# 2_Airframe-Power_2_-_Old.net
KiCad netlist of a schematic drawn in Altium Designer
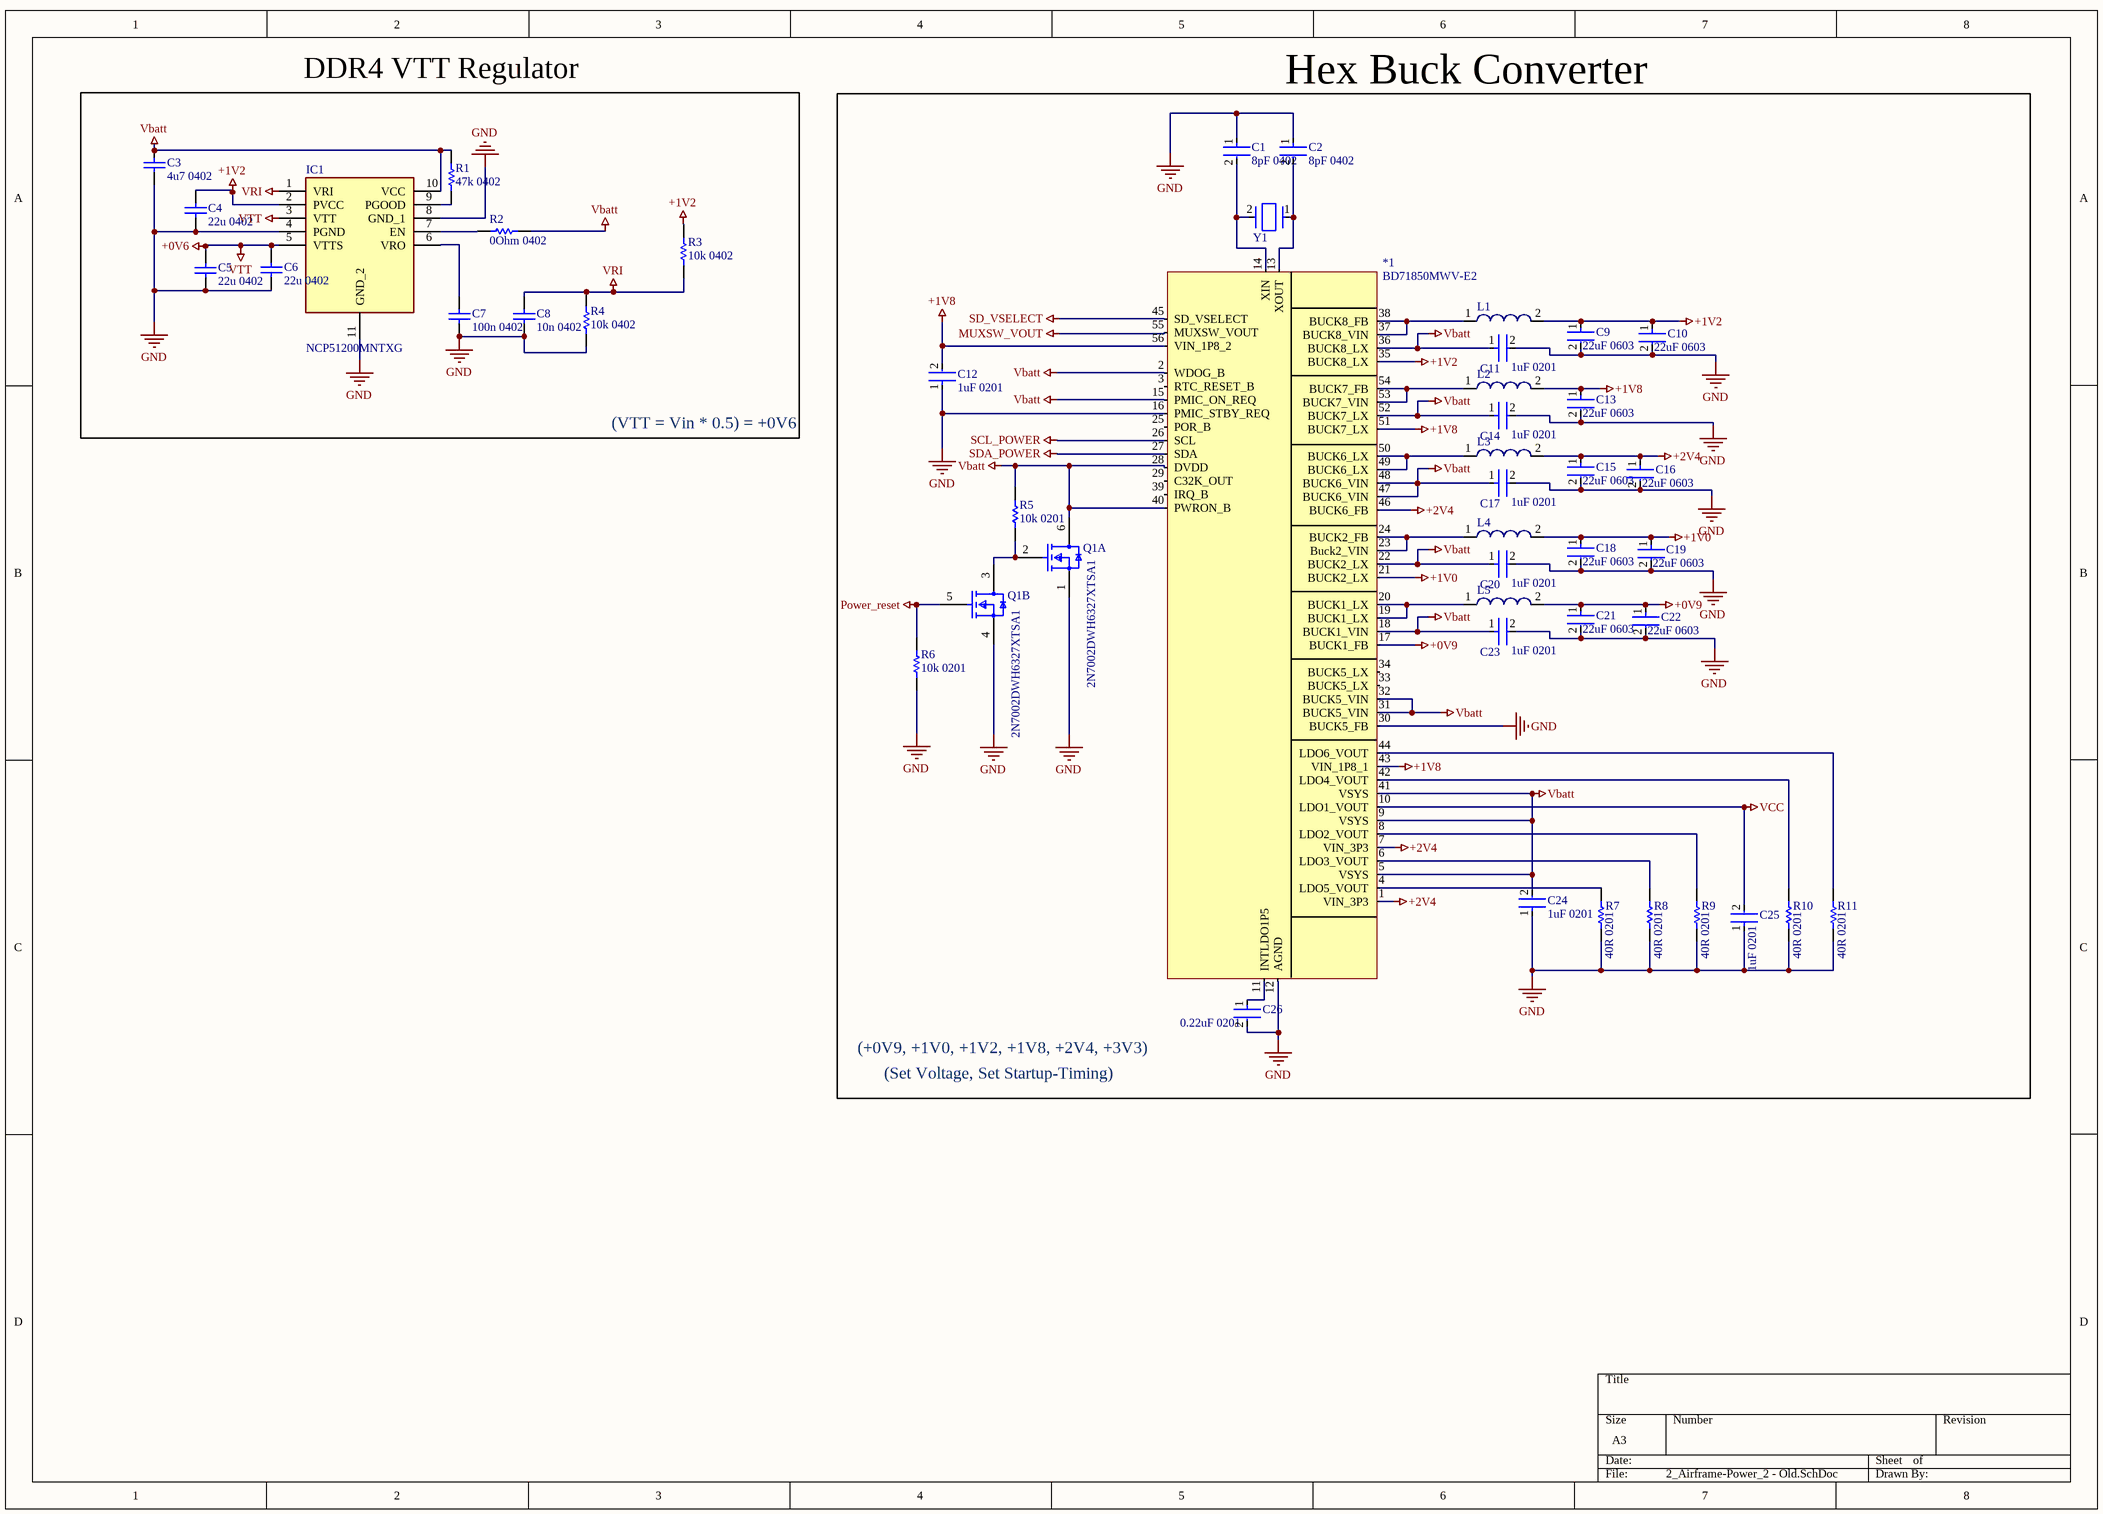
[diagram p0: 2_Airframe-Power_2 - Old.SchDoc]

(export (version "E")
  (design (tool "Eeschema 10.0.6"))
  (components
    (comp (ref "*1")
      (value "BD71850MWV-E2")
      (footprint "QFN40P700X700X80_HS-57N")
      (libsource (lib "Projects") (part "BD71850MWV-E2-Symbol-1"))
    )
    (comp (ref "C1")
      (value "8pF 0402")
      (footprint "FP-C0402C225M9PACTU-MFG")
      (description "CAP CER 2.2UF 6.3V X5R 0402")
      (fields (field (name "VOLTAGE") "6.3V") (field (name "TOLERANCE") "20%"))
      (libsource (lib "Altium Content Vault") (part "b4654b650e69147ec39a6b967a45e02"))
    )
    (comp (ref "C2")
      (value "8pF 0402")
      (footprint "FP-C0402C225M9PACTU-MFG")
      (description "CAP CER 2.2UF 6.3V X5R 0402")
      (fields (field (name "VOLTAGE") "6.3V") (field (name "TOLERANCE") "20%"))
      (libsource (lib "Altium Content Vault") (part "b4654b650e69147ec39a6b967a45e02"))
    )
    (comp (ref "C3")
      (value "4u7 0402")
      (footprint "CAPC1005X55X25ML5T10")
      (description "Chip Capacitor, 1 nF, +/- 10%, 50 V, -55 to 125 degC, 0402 (1005 Metric), RoHS, Tape and Reel")
      (fields (field (name "TOLERANCE") "10%"))
      (libsource (lib "Altium Content Vault") (part "CAP-NP-2"))
    )
    (comp (ref "C4")
      (value "22u 0402")
      (footprint "CAPC1005X55X25ML5T10")
      (description "Chip Capacitor, 1 nF, +/- 10%, 50 V, -55 to 125 degC, 0402 (1005 Metric), RoHS, Tape and Reel")
      (fields (field (name "TOLERANCE") "10%"))
      (libsource (lib "Altium Content Vault") (part "CAP-NP-2"))
    )
    (comp (ref "C5")
      (value "22u 0402")
      (footprint "CAPC1005X55X25ML5T10")
      (description "Chip Capacitor, 1 nF, +/- 10%, 50 V, -55 to 125 degC, 0402 (1005 Metric), RoHS, Tape and Reel")
      (fields (field (name "TOLERANCE") "10%"))
      (libsource (lib "Altium Content Vault") (part "CAP-NP-2"))
    )
    (comp (ref "C6")
      (value "22u 0402")
      (footprint "CAPC1005X55X25ML5T10")
      (description "Chip Capacitor, 1 nF, +/- 10%, 50 V, -55 to 125 degC, 0402 (1005 Metric), RoHS, Tape and Reel")
      (fields (field (name "TOLERANCE") "10%"))
      (libsource (lib "Altium Content Vault") (part "CAP-NP-2"))
    )
    (comp (ref "C7")
      (value "100n 0402")
      (footprint "CAPC1005X55X25ML5T10")
      (description "Chip Capacitor, 1 nF, +/- 10%, 50 V, -55 to 125 degC, 0402 (1005 Metric), RoHS, Tape and Reel")
      (fields (field (name "TOLERANCE") "10%"))
      (libsource (lib "Altium Content Vault") (part "CAP-NP-2"))
    )
    (comp (ref "C8")
      (value "10n 0402")
      (footprint "CAPC1005X55X25ML5T10")
      (description "Chip Capacitor, 1 nF, +/- 10%, 50 V, -55 to 125 degC, 0402 (1005 Metric), RoHS, Tape and Reel")
      (fields (field (name "TOLERANCE") "10%"))
      (libsource (lib "Altium Content Vault") (part "CAP-NP-2"))
    )
    (comp (ref "C9")
      (value "22uF 0603")
      (footprint "FP-GRM188-0_2-IPC_C")
      (description "Chip Multilayer Ceramic Capacitors for General Purpose, 0603, 22uF, X5R, 15%, 20%, 10V")
      (fields (field (name "TOLERANCE") "20%"))
      (libsource (lib "Altium Content Vault") (part "11868f565c42a9108669ba33697ecf6"))
    )
    (comp (ref "C10")
      (value "22uF 0603")
      (footprint "FP-GRM188-0_2-IPC_C")
      (description "Chip Multilayer Ceramic Capacitors for General Purpose, 0603, 22uF, X5R, 15%, 20%, 10V")
      (fields (field (name "TOLERANCE") "20%"))
      (libsource (lib "Altium Content Vault") (part "11868f565c42a9108669ba33697ecf6"))
    )
    (comp (ref "C11")
      (value "1uF 0201")
      (footprint "FP-C0603-030-0_03-IPC_C")
      (description "Multilayer Ceramic Capacitors 220nF ±10% 6.3V X6S SMD 0201")
      (fields (field (name "TOLERANCE") "10%"))
      (libsource (lib "Altium Content Vault") (part "02cd4be3c70576c341d710602a673aa"))
    )
    (comp (ref "C12")
      (value "1uF 0201")
      (footprint "FP-C0603-030-0_03-IPC_C")
      (description "Multilayer Ceramic Capacitors 220nF ±10% 6.3V X6S SMD 0201")
      (fields (field (name "TOLERANCE") "10%"))
      (libsource (lib "Altium Content Vault") (part "02cd4be3c70576c341d710602a673aa"))
    )
    (comp (ref "C13")
      (value "22uF 0603")
      (footprint "FP-GRM188-0_2-IPC_C")
      (description "Chip Multilayer Ceramic Capacitors for General Purpose, 0603, 22uF, X5R, 15%, 20%, 10V")
      (fields (field (name "TOLERANCE") "20%"))
      (libsource (lib "Altium Content Vault") (part "11868f565c42a9108669ba33697ecf6"))
    )
    (comp (ref "C14")
      (value "1uF 0201")
      (footprint "FP-C0603-030-0_03-IPC_C")
      (description "Multilayer Ceramic Capacitors 220nF ±10% 6.3V X6S SMD 0201")
      (fields (field (name "TOLERANCE") "10%"))
      (libsource (lib "Altium Content Vault") (part "02cd4be3c70576c341d710602a673aa"))
    )
    (comp (ref "C15")
      (value "22uF 0603")
      (footprint "FP-GRM188-0_2-IPC_C")
      (description "Chip Multilayer Ceramic Capacitors for General Purpose, 0603, 22uF, X5R, 15%, 20%, 10V")
      (fields (field (name "TOLERANCE") "20%"))
      (libsource (lib "Altium Content Vault") (part "11868f565c42a9108669ba33697ecf6"))
    )
    (comp (ref "C16")
      (value "22uF 0603")
      (footprint "FP-GRM188-0_2-IPC_C")
      (description "Chip Multilayer Ceramic Capacitors for General Purpose, 0603, 22uF, X5R, 15%, 20%, 10V")
      (fields (field (name "TOLERANCE") "20%"))
      (libsource (lib "Altium Content Vault") (part "11868f565c42a9108669ba33697ecf6"))
    )
    (comp (ref "C17")
      (value "1uF 0201")
      (footprint "FP-C0603-030-0_03-IPC_C")
      (description "Multilayer Ceramic Capacitors 220nF ±10% 6.3V X6S SMD 0201")
      (fields (field (name "TOLERANCE") "10%"))
      (libsource (lib "Altium Content Vault") (part "02cd4be3c70576c341d710602a673aa"))
    )
    (comp (ref "C18")
      (value "22uF 0603")
      (footprint "FP-GRM188-0_2-IPC_C")
      (description "Chip Multilayer Ceramic Capacitors for General Purpose, 0603, 22uF, X5R, 15%, 20%, 10V")
      (fields (field (name "TOLERANCE") "20%"))
      (libsource (lib "Altium Content Vault") (part "11868f565c42a9108669ba33697ecf6"))
    )
    (comp (ref "C19")
      (value "22uF 0603")
      (footprint "FP-GRM188-0_2-IPC_C")
      (description "Chip Multilayer Ceramic Capacitors for General Purpose, 0603, 22uF, X5R, 15%, 20%, 10V")
      (fields (field (name "TOLERANCE") "20%"))
      (libsource (lib "Altium Content Vault") (part "11868f565c42a9108669ba33697ecf6"))
    )
    (comp (ref "C20")
      (value "1uF 0201")
      (footprint "FP-C0603-030-0_03-IPC_C")
      (description "Multilayer Ceramic Capacitors 220nF ±10% 6.3V X6S SMD 0201")
      (fields (field (name "TOLERANCE") "10%"))
      (libsource (lib "Altium Content Vault") (part "02cd4be3c70576c341d710602a673aa"))
    )
    (comp (ref "C21")
      (value "22uF 0603")
      (footprint "FP-GRM188-0_2-IPC_C")
      (description "Chip Multilayer Ceramic Capacitors for General Purpose, 0603, 22uF, X5R, 15%, 20%, 10V")
      (fields (field (name "TOLERANCE") "20%"))
      (libsource (lib "Altium Content Vault") (part "11868f565c42a9108669ba33697ecf6"))
    )
    (comp (ref "C22")
      (value "22uF 0603")
      (footprint "FP-GRM188-0_2-IPC_C")
      (description "Chip Multilayer Ceramic Capacitors for General Purpose, 0603, 22uF, X5R, 15%, 20%, 10V")
      (fields (field (name "TOLERANCE") "20%"))
      (libsource (lib "Altium Content Vault") (part "11868f565c42a9108669ba33697ecf6"))
    )
    (comp (ref "C23")
      (value "1uF 0201")
      (footprint "FP-C0603-030-0_03-IPC_C")
      (description "Multilayer Ceramic Capacitors 220nF ±10% 6.3V X6S SMD 0201")
      (fields (field (name "TOLERANCE") "10%"))
      (libsource (lib "Altium Content Vault") (part "02cd4be3c70576c341d710602a673aa"))
    )
    (comp (ref "C24")
      (value "1uF 0201")
      (footprint "FP-C0603-030-0_03-IPC_C")
      (description "Multilayer Ceramic Capacitors 220nF ±10% 6.3V X6S SMD 0201")
      (fields (field (name "TOLERANCE") "10%"))
      (libsource (lib "Altium Content Vault") (part "02cd4be3c70576c341d710602a673aa"))
    )
    (comp (ref "C25")
      (value "1uF 0201")
      (footprint "FP-C0603-030-0_03-IPC_C")
      (description "Multilayer Ceramic Capacitors 220nF ±10% 6.3V X6S SMD 0201")
      (fields (field (name "TOLERANCE") "10%"))
      (libsource (lib "Altium Content Vault") (part "02cd4be3c70576c341d710602a673aa"))
    )
    (comp (ref "C26")
      (value "0.22uF 0201")
      (footprint "FP-C0603-030-0_03-IPC_C")
      (description "Multilayer Ceramic Capacitors 220nF ±10% 6.3V X6S SMD 0201")
      (fields (field (name "TOLERANCE") "10%"))
      (libsource (lib "Altium Content Vault") (part "02cd4be3c70576c341d710602a673aa"))
    )
    (comp (ref "IC1")
      (value "NCP51200MNTXG")
      (footprint "SamacSys:SON50P300X300X100-11N")
      (description "Integrated Circuit")
      (fields (field (name "MOUSER PART NUMBER") "863-NCP51200MNTXG"))
      (libsource (lib "*") (part "NCP51200MNTXG"))
    )
    (comp (ref "L1")
      (value "744040320047")
      (footprint "WE-LQS 3015")
      (description "WE-LQS SMD Power Inductor, L=0.47")
      (fields (field (name "MANUFACTURER") "Wuerth Elektronik"))
      (libsource (lib "Altium Content Vault") (part "WE-IND-INDUCTOR-2"))
    )
    (comp (ref "L2")
      (value "744040320047")
      (footprint "WE-LQS 3015")
      (description "WE-LQS SMD Power Inductor, L=0.47")
      (fields (field (name "MANUFACTURER") "Wuerth Elektronik"))
      (libsource (lib "Altium Content Vault") (part "WE-IND-INDUCTOR-2"))
    )
    (comp (ref "L3")
      (value "744040320047")
      (footprint "WE-LQS 3015")
      (description "WE-LQS SMD Power Inductor, L=0.47")
      (fields (field (name "MANUFACTURER") "Wuerth Elektronik"))
      (libsource (lib "Altium Content Vault") (part "WE-IND-INDUCTOR-2"))
    )
    (comp (ref "L4")
      (value "744040320047")
      (footprint "WE-LQS 3015")
      (description "WE-LQS SMD Power Inductor, L=0.47")
      (fields (field (name "MANUFACTURER") "Wuerth Elektronik"))
      (libsource (lib "Altium Content Vault") (part "WE-IND-INDUCTOR-2"))
    )
    (comp (ref "L5")
      (value "744040320047")
      (footprint "WE-LQS 3015")
      (description "WE-LQS SMD Power Inductor, L=0.47")
      (fields (field (name "MANUFACTURER") "Wuerth Elektronik"))
      (libsource (lib "Altium Content Vault") (part "WE-IND-INDUCTOR-2"))
    )
    (comp (ref "Q1")
      (value "2N7002DWH6327XTSA1")
      (footprint "FP-PG-SOT363-6-MFG")
      (description "MOSFET 2N-CH 60V 0.3A SOT363")
      (libsource (lib "Altium Content Vault") (part "226acf62e6c56029797c43a6c48a86b"))
    )
    (comp (ref "R1")
      (value "47k 0402")
      (footprint "RESC1608X55X25ML10T15")
      (fields (field (name "TOLERANCE") "5%") (field (name "MANUFACTURER") "Yageo"))
      (libsource (lib "Altium Content Vault") (part "RES-2"))
    )
    (comp (ref "R2")
      (value "0Ohm 0402")
      (footprint "RESC1608X55X25ML10T15")
      (description "Chip Resistor, 0 Ohm, +/- 5%, 0.1 W, -55 to 155 degC, 0603 (1608 Metric), RoHS, Tape and Reel")
      (fields (field (name "TOLERANCE") "5%") (field (name "MANUFACTURER") "Yageo"))
      (libsource (lib "Altium Content Vault") (part "RES-2"))
    )
    (comp (ref "R3")
      (value "10k 0402")
      (footprint "RESC1608X55X25ML10T15")
      (fields (field (name "TOLERANCE") "5%") (field (name "MANUFACTURER") "Yageo"))
      (libsource (lib "Altium Content Vault") (part "RES-2"))
    )
    (comp (ref "R4")
      (value "10k 0402")
      (footprint "RESC1608X55X25ML10T15")
      (fields (field (name "TOLERANCE") "5%") (field (name "MANUFACTURER") "Yageo"))
      (libsource (lib "Altium Content Vault") (part "RES-2"))
    )
    (comp (ref "R5")
      (value "10k 0201")
      (footprint "RESC0603X28X15NL05T05")
      (fields (field (name "MANUFACTURER") "Vishay Dale") (field (name "PART NUMBER") "CRCW020110K0FNED"))
      (libsource (lib "Altium Content Vault") (part "RES"))
    )
    (comp (ref "R6")
      (value "10k 0201")
      (footprint "RESC0603X28X15NL05T05")
      (fields (field (name "MANUFACTURER") "Vishay Dale") (field (name "PART NUMBER") "CRCW020110K0FNED"))
      (libsource (lib "Altium Content Vault") (part "RES"))
    )
    (comp (ref "R7")
      (value "40R 0201")
      (footprint "RESC0603X28X15NL05T05")
      (fields (field (name "MANUFACTURER") "Vishay") (field (name "PART NUMBER") "CRCW0201100RFNED"))
      (libsource (lib "Altium Content Vault") (part "RES"))
    )
    (comp (ref "R8")
      (value "40R 0201")
      (footprint "RESC0603X28X15NL05T05")
      (fields (field (name "MANUFACTURER") "Vishay") (field (name "PART NUMBER") "CRCW0201100RFNED"))
      (libsource (lib "Altium Content Vault") (part "RES"))
    )
    (comp (ref "R9")
      (value "40R 0201")
      (footprint "RESC0603X28X15NL05T05")
      (fields (field (name "MANUFACTURER") "Vishay") (field (name "PART NUMBER") "CRCW0201100RFNED"))
      (libsource (lib "Altium Content Vault") (part "RES"))
    )
    (comp (ref "R10")
      (value "40R 0201")
      (footprint "RESC0603X28X15NL05T05")
      (fields (field (name "MANUFACTURER") "Vishay") (field (name "PART NUMBER") "CRCW0201100RFNED"))
      (libsource (lib "Altium Content Vault") (part "RES"))
    )
    (comp (ref "R11")
      (value "40R 0201")
      (footprint "RESC0603X28X15NL05T05")
      (fields (field (name "MANUFACTURER") "Vishay") (field (name "PART NUMBER") "CRCW0201100RFNED"))
      (libsource (lib "Altium Content Vault") (part "RES"))
    )
    (comp (ref "Y1")
      (value "ABS06-32.768KHZ-9-T")
      (footprint "FP-ABS06-MFG")
      (description "Crystal 32.768kHz ±20ppm (Tol) 9pF FUND 90kΩ 2-Pin Mini-CSMD T/R")
      (fields (field (name "TOLERANCE") "20ppm"))
      (libsource (lib "Altium Content Vault") (part "c23a69dc6c9e2f18f2079038eb95dd1"))
    )
  )
  (nets
    (net (code "1") (name "+0V6") (class "Default")
      (node (ref "C5") (pin "1") (pinfunction "1_1") (pintype "passive"))
      (node (ref "C6") (pin "1") (pinfunction "1_1") (pintype "passive"))
      (node (ref "IC1") (pin "3") (pinfunction "VTT_3") (pintype "passive"))
      (node (ref "IC1") (pin "5") (pinfunction "VTTS_5") (pintype "passive"))
    )
    (net (code "2") (name "+0V9") (class "Default")
      (node (ref "*1") (pin "17") (pinfunction "BUCK1_FB_17") (pintype "input"))
      (node (ref "C21") (pin "1") (pinfunction "1_1") (pintype "passive"))
      (node (ref "C22") (pin "1") (pinfunction "1_1") (pintype "passive"))
      (node (ref "L5") (pin "2") (pinfunction "2_2") (pintype "passive"))
    )
    (net (code "3") (name "+1V0") (class "Default")
      (node (ref "*1") (pin "21") (pinfunction "BUCK2_LX_21") (pintype "input"))
      (node (ref "C18") (pin "1") (pinfunction "1_1") (pintype "passive"))
      (node (ref "C19") (pin "1") (pinfunction "1_1") (pintype "passive"))
      (node (ref "L4") (pin "2") (pinfunction "2_2") (pintype "passive"))
    )
    (net (code "4") (name "+1V2") (class "Default")
      (node (ref "*1") (pin "35") (pinfunction "BUCK8_LX_35") (pintype "input"))
      (node (ref "C10") (pin "1") (pinfunction "1_1") (pintype "passive"))
      (node (ref "C4") (pin "1") (pinfunction "1_1") (pintype "passive"))
      (node (ref "C9") (pin "1") (pinfunction "1_1") (pintype "passive"))
      (node (ref "IC1") (pin "2") (pinfunction "PVCC_2") (pintype "passive"))
      (node (ref "L1") (pin "2") (pinfunction "2_2") (pintype "passive"))
      (node (ref "R3") (pin "1") (pinfunction "1_1") (pintype "passive"))
    )
    (net (code "5") (name "+1V8") (class "Default")
      (node (ref "*1") (pin "43") (pinfunction "VIN_1P8_1_43") (pintype "input"))
      (node (ref "*1") (pin "51") (pinfunction "BUCK7_LX_51") (pintype "input"))
      (node (ref "*1") (pin "56") (pinfunction "VIN_1P8_2_56") (pintype "input"))
      (node (ref "C12") (pin "2") (pinfunction "2_2") (pintype "passive"))
      (node (ref "C13") (pin "1") (pinfunction "1_1") (pintype "passive"))
      (node (ref "L2") (pin "2") (pinfunction "2_2") (pintype "passive"))
    )
    (net (code "6") (name "+2V4") (class "Default")
      (node (ref "*1") (pin "1") (pinfunction "VIN_3P3_1") (pintype "input"))
      (node (ref "*1") (pin "46") (pinfunction "BUCK6_FB_46") (pintype "input"))
      (node (ref "*1") (pin "7") (pinfunction "VIN_3P3_7") (pintype "input"))
      (node (ref "C15") (pin "1") (pinfunction "1_1") (pintype "passive"))
      (node (ref "C16") (pin "1") (pinfunction "1_1") (pintype "passive"))
      (node (ref "L3") (pin "2") (pinfunction "2_2") (pintype "passive"))
    )
    (net (code "7") (name "GND") (class "Default")
      (node (ref "*1") (pin "12") (pinfunction "AGND_12") (pintype "input"))
      (node (ref "*1") (pin "16") (pinfunction "PMIC_STBY_REQ_16") (pintype "input"))
      (node (ref "*1") (pin "30") (pinfunction "BUCK5_FB_30") (pintype "input"))
      (node (ref "C1") (pin "1") (pinfunction "1_1") (pintype "passive"))
      (node (ref "C10") (pin "2") (pinfunction "2_2") (pintype "passive"))
      (node (ref "C11") (pin "2") (pinfunction "2_2") (pintype "passive"))
      (node (ref "C12") (pin "1") (pinfunction "1_1") (pintype "passive"))
      (node (ref "C13") (pin "2") (pinfunction "2_2") (pintype "passive"))
      (node (ref "C14") (pin "2") (pinfunction "2_2") (pintype "passive"))
      (node (ref "C15") (pin "2") (pinfunction "2_2") (pintype "passive"))
      (node (ref "C16") (pin "2") (pinfunction "2_2") (pintype "passive"))
      (node (ref "C17") (pin "2") (pinfunction "2_2") (pintype "passive"))
      (node (ref "C18") (pin "2") (pinfunction "2_2") (pintype "passive"))
      (node (ref "C19") (pin "2") (pinfunction "2_2") (pintype "passive"))
      (node (ref "C2") (pin "1") (pinfunction "1_1") (pintype "passive"))
      (node (ref "C20") (pin "2") (pinfunction "2_2") (pintype "passive"))
      (node (ref "C21") (pin "2") (pinfunction "2_2") (pintype "passive"))
      (node (ref "C22") (pin "2") (pinfunction "2_2") (pintype "passive"))
      (node (ref "C23") (pin "2") (pinfunction "2_2") (pintype "passive"))
      (node (ref "C24") (pin "1") (pinfunction "1_1") (pintype "passive"))
      (node (ref "C25") (pin "1") (pinfunction "1_1") (pintype "passive"))
      (node (ref "C26") (pin "2") (pinfunction "2_2") (pintype "passive"))
      (node (ref "C3") (pin "2") (pinfunction "2_2") (pintype "passive"))
      (node (ref "C4") (pin "2") (pinfunction "2_2") (pintype "passive"))
      (node (ref "C5") (pin "2") (pinfunction "2_2") (pintype "passive"))
      (node (ref "C6") (pin "2") (pinfunction "2_2") (pintype "passive"))
      (node (ref "C7") (pin "2") (pinfunction "2_2") (pintype "passive"))
      (node (ref "C8") (pin "2") (pinfunction "2_2") (pintype "passive"))
      (node (ref "C9") (pin "2") (pinfunction "2_2") (pintype "passive"))
      (node (ref "IC1") (pin "11") (pinfunction "GND_2_11") (pintype "passive"))
      (node (ref "IC1") (pin "4") (pinfunction "PGND_4") (pintype "passive"))
      (node (ref "IC1") (pin "8") (pinfunction "GND_1_8") (pintype "passive"))
      (node (ref "Q1") (pin "1") (pinfunction "S1_1") (pintype "passive"))
      (node (ref "Q1") (pin "4") (pinfunction "S2_4") (pintype "passive"))
      (node (ref "R10") (pin "1") (pinfunction "1_1") (pintype "passive"))
      (node (ref "R11") (pin "1") (pinfunction "1_1") (pintype "passive"))
      (node (ref "R4") (pin "2") (pinfunction "2_2") (pintype "passive"))
      (node (ref "R6") (pin "1") (pinfunction "1_1") (pintype "passive"))
      (node (ref "R7") (pin "1") (pinfunction "1_1") (pintype "passive"))
      (node (ref "R8") (pin "1") (pinfunction "1_1") (pintype "passive"))
      (node (ref "R9") (pin "1") (pinfunction "1_1") (pintype "passive"))
    )
    (net (code "8") (name "MUXSW_VOUT") (class "Default")
      (node (ref "*1") (pin "55") (pinfunction "MUXSW_VOUT_55") (pintype "input"))
    )
    (net (code "9") (name "Net-(*1-BUCK1_LX-Pad19)") (class "Default")
      (node (ref "*1") (pin "19") (pinfunction "BUCK1_LX_19") (pintype "input"))
      (node (ref "*1") (pin "20") (pinfunction "BUCK1_LX_20") (pintype "input"))
      (node (ref "L5") (pin "1") (pinfunction "1_1") (pintype "passive"))
    )
    (net (code "10") (name "Net-(*1-BUCK2_FB)") (class "Default")
      (node (ref "*1") (pin "23") (pinfunction "Buck2_VIN_23") (pintype "input"))
      (node (ref "*1") (pin "24") (pinfunction "BUCK2_FB_24") (pintype "input"))
      (node (ref "L4") (pin "1") (pinfunction "1_1") (pintype "passive"))
    )
    (net (code "11") (name "Net-(*1-BUCK6_LX-Pad49)") (class "Default")
      (node (ref "*1") (pin "49") (pinfunction "BUCK6_LX_49") (pintype "input"))
      (node (ref "*1") (pin "50") (pinfunction "BUCK6_LX_50") (pintype "input"))
      (node (ref "L3") (pin "1") (pinfunction "1_1") (pintype "passive"))
    )
    (net (code "12") (name "Net-(*1-BUCK7_FB)") (class "Default")
      (node (ref "*1") (pin "53") (pinfunction "BUCK7_VIN_53") (pintype "input"))
      (node (ref "*1") (pin "54") (pinfunction "BUCK7_FB_54") (pintype "input"))
      (node (ref "L2") (pin "1") (pinfunction "1_1") (pintype "passive"))
    )
    (net (code "13") (name "Net-(*1-BUCK8_FB)") (class "Default")
      (node (ref "*1") (pin "37") (pinfunction "BUCK8_VIN_37") (pintype "input"))
      (node (ref "*1") (pin "38") (pinfunction "BUCK8_FB_38") (pintype "input"))
      (node (ref "L1") (pin "1") (pinfunction "1_1") (pintype "passive"))
    )
    (net (code "14") (name "Net-(*1-INTLDO1P5)") (class "Default")
      (node (ref "*1") (pin "11") (pinfunction "INTLDO1P5_11") (pintype "input"))
      (node (ref "C26") (pin "1") (pinfunction "1_1") (pintype "passive"))
    )
    (net (code "15") (name "Net-(*1-LDO2_VOUT)") (class "Default")
      (node (ref "*1") (pin "8") (pinfunction "LDO2_VOUT_8") (pintype "input"))
      (node (ref "R9") (pin "2") (pinfunction "2_2") (pintype "passive"))
    )
    (net (code "16") (name "Net-(*1-LDO3_VOUT)") (class "Default")
      (node (ref "*1") (pin "6") (pinfunction "LDO3_VOUT_6") (pintype "input"))
      (node (ref "R8") (pin "2") (pinfunction "2_2") (pintype "passive"))
    )
    (net (code "17") (name "Net-(*1-LDO4_VOUT)") (class "Default")
      (node (ref "*1") (pin "42") (pinfunction "LDO4_VOUT_42") (pintype "input"))
      (node (ref "R10") (pin "2") (pinfunction "2_2") (pintype "passive"))
    )
    (net (code "18") (name "Net-(*1-LDO5_VOUT)") (class "Default")
      (node (ref "*1") (pin "4") (pinfunction "LDO5_VOUT_4") (pintype "input"))
      (node (ref "R7") (pin "2") (pinfunction "2_2") (pintype "passive"))
    )
    (net (code "19") (name "Net-(*1-LDO6_VOUT)") (class "Default")
      (node (ref "*1") (pin "44") (pinfunction "LDO6_VOUT_44") (pintype "input"))
      (node (ref "R11") (pin "2") (pinfunction "2_2") (pintype "passive"))
    )
    (net (code "20") (name "Net-(*1-XIN)") (class "Default")
      (node (ref "*1") (pin "14") (pinfunction "XIN_14") (pintype "input"))
      (node (ref "C1") (pin "2") (pinfunction "2_2") (pintype "passive"))
      (node (ref "Y1") (pin "2") (pinfunction "2_2") (pintype "passive"))
    )
    (net (code "21") (name "Net-(*1-XOUT)") (class "Default")
      (node (ref "*1") (pin "13") (pinfunction "XOUT_13") (pintype "input"))
      (node (ref "C2") (pin "2") (pinfunction "2_2") (pintype "passive"))
      (node (ref "Y1") (pin "1") (pinfunction "1_1") (pintype "passive"))
    )
    (net (code "22") (name "Net-(IC1-EN)") (class "Default")
      (node (ref "IC1") (pin "7") (pinfunction "EN_7") (pintype "passive"))
      (node (ref "R2") (pin "2") (pinfunction "2_2") (pintype "passive"))
    )
    (net (code "23") (name "Net-(IC1-PGOOD)") (class "Default")
      (node (ref "IC1") (pin "9") (pinfunction "PGOOD_9") (pintype "passive"))
      (node (ref "R1") (pin "1") (pinfunction "1_1") (pintype "passive"))
    )
    (net (code "24") (name "Net-(IC1-VRO)") (class "Default")
      (node (ref "C7") (pin "1") (pinfunction "1_1") (pintype "passive"))
      (node (ref "IC1") (pin "6") (pinfunction "VRO_6") (pintype "passive"))
    )
    (net (code "25") (name "Net-(Q1A-G1)") (class "Default")
      (node (ref "Q1") (pin "2") (pinfunction "G1_2") (pintype "passive"))
      (node (ref "Q1") (pin "3") (pinfunction "D2_3") (pintype "passive"))
      (node (ref "R5") (pin "1") (pinfunction "1_1") (pintype "passive"))
    )
    (net (code "26") (name "Power_reset") (class "Default")
      (node (ref "Q1") (pin "5") (pinfunction "G2_5") (pintype "passive"))
      (node (ref "R6") (pin "2") (pinfunction "2_2") (pintype "passive"))
    )
    (net (code "27") (name "SCL_POWER") (class "Default")
      (node (ref "*1") (pin "26") (pinfunction "SCL_26") (pintype "input"))
    )
    (net (code "28") (name "SDA_POWER") (class "Default")
      (node (ref "*1") (pin "27") (pinfunction "SDA_27") (pintype "input"))
    )
    (net (code "29") (name "SD_VSELECT") (class "Default")
      (node (ref "*1") (pin "45") (pinfunction "SD_VSELECT_45") (pintype "input"))
    )
    (net (code "30") (name "VCC") (class "Default")
      (node (ref "*1") (pin "10") (pinfunction "LDO1_VOUT_10") (pintype "input"))
      (node (ref "C25") (pin "2") (pinfunction "2_2") (pintype "passive"))
    )
    (net (code "31") (name "VRI") (class "Default")
      (node (ref "C8") (pin "1") (pinfunction "1_1") (pintype "passive"))
      (node (ref "IC1") (pin "1") (pinfunction "VRI_1") (pintype "passive"))
      (node (ref "R3") (pin "2") (pinfunction "2_2") (pintype "passive"))
      (node (ref "R4") (pin "1") (pinfunction "1_1") (pintype "passive"))
    )
    (net (code "32") (name "Vbatt") (class "Default")
      (node (ref "*1") (pin "15") (pinfunction "PMIC_ON_REQ_15") (pintype "input"))
      (node (ref "*1") (pin "18") (pinfunction "BUCK1_VIN_18") (pintype "input"))
      (node (ref "*1") (pin "2") (pinfunction "WDOG_B_2") (pintype "input"))
      (node (ref "*1") (pin "22") (pinfunction "BUCK2_LX_22") (pintype "input"))
      (node (ref "*1") (pin "28") (pinfunction "DVDD_28") (pintype "input"))
      (node (ref "*1") (pin "31") (pinfunction "BUCK5_VIN_31") (pintype "input"))
      (node (ref "*1") (pin "32") (pinfunction "BUCK5_VIN_32") (pintype "input"))
      (node (ref "*1") (pin "36") (pinfunction "BUCK8_LX_36") (pintype "input"))
      (node (ref "*1") (pin "40") (pinfunction "PWRON_B_40") (pintype "input"))
      (node (ref "*1") (pin "41") (pinfunction "VSYS_41") (pintype "input"))
      (node (ref "*1") (pin "47") (pinfunction "BUCK6_VIN_47") (pintype "input"))
      (node (ref "*1") (pin "48") (pinfunction "BUCK6_VIN_48") (pintype "input"))
      (node (ref "*1") (pin "5") (pinfunction "VSYS_5") (pintype "input"))
      (node (ref "*1") (pin "52") (pinfunction "BUCK7_LX_52") (pintype "input"))
      (node (ref "*1") (pin "9") (pinfunction "VSYS_9") (pintype "input"))
      (node (ref "C11") (pin "1") (pinfunction "1_1") (pintype "passive"))
      (node (ref "C14") (pin "1") (pinfunction "1_1") (pintype "passive"))
      (node (ref "C17") (pin "1") (pinfunction "1_1") (pintype "passive"))
      (node (ref "C20") (pin "1") (pinfunction "1_1") (pintype "passive"))
      (node (ref "C23") (pin "1") (pinfunction "1_1") (pintype "passive"))
      (node (ref "C24") (pin "2") (pinfunction "2_2") (pintype "passive"))
      (node (ref "C3") (pin "1") (pinfunction "1_1") (pintype "passive"))
      (node (ref "IC1") (pin "10") (pinfunction "VCC_10") (pintype "passive"))
      (node (ref "Q1") (pin "6") (pinfunction "D1_6") (pintype "passive"))
      (node (ref "R1") (pin "2") (pinfunction "2_2") (pintype "passive"))
      (node (ref "R2") (pin "1") (pinfunction "1_1") (pintype "passive"))
      (node (ref "R5") (pin "2") (pinfunction "2_2") (pintype "passive"))
    )
    (net (code "33") (name "unconnected-(*1-BUCK5_LX-Pad33)") (class "Default")
      (node (ref "*1") (pin "33") (pinfunction "BUCK5_LX_33") (pintype "input"))
    )
    (net (code "34") (name "unconnected-(*1-BUCK5_LX-Pad34)") (class "Default")
      (node (ref "*1") (pin "34") (pinfunction "BUCK5_LX_34") (pintype "input"))
    )
    (net (code "35") (name "unconnected-(*1-C32K_OUT-Pad29)") (class "Default")
      (node (ref "*1") (pin "29") (pinfunction "C32K_OUT_29") (pintype "input"))
    )
    (net (code "36") (name "unconnected-(*1-IRQ_B-Pad39)") (class "Default")
      (node (ref "*1") (pin "39") (pinfunction "IRQ_B_39") (pintype "input"))
    )
    (net (code "37") (name "unconnected-(*1-POR_B-Pad25)") (class "Default")
      (node (ref "*1") (pin "25") (pinfunction "POR_B_25") (pintype "input"))
    )
    (net (code "38") (name "unconnected-(*1-RTC_RESET_B-Pad3)") (class "Default")
      (node (ref "*1") (pin "3") (pinfunction "RTC_RESET_B_3") (pintype "input"))
    )
  )
)
